# SCH_Espejo_Pcb_tof_2023-06-20.net
KiCad netlist of a schematic drawn in EasyEDA
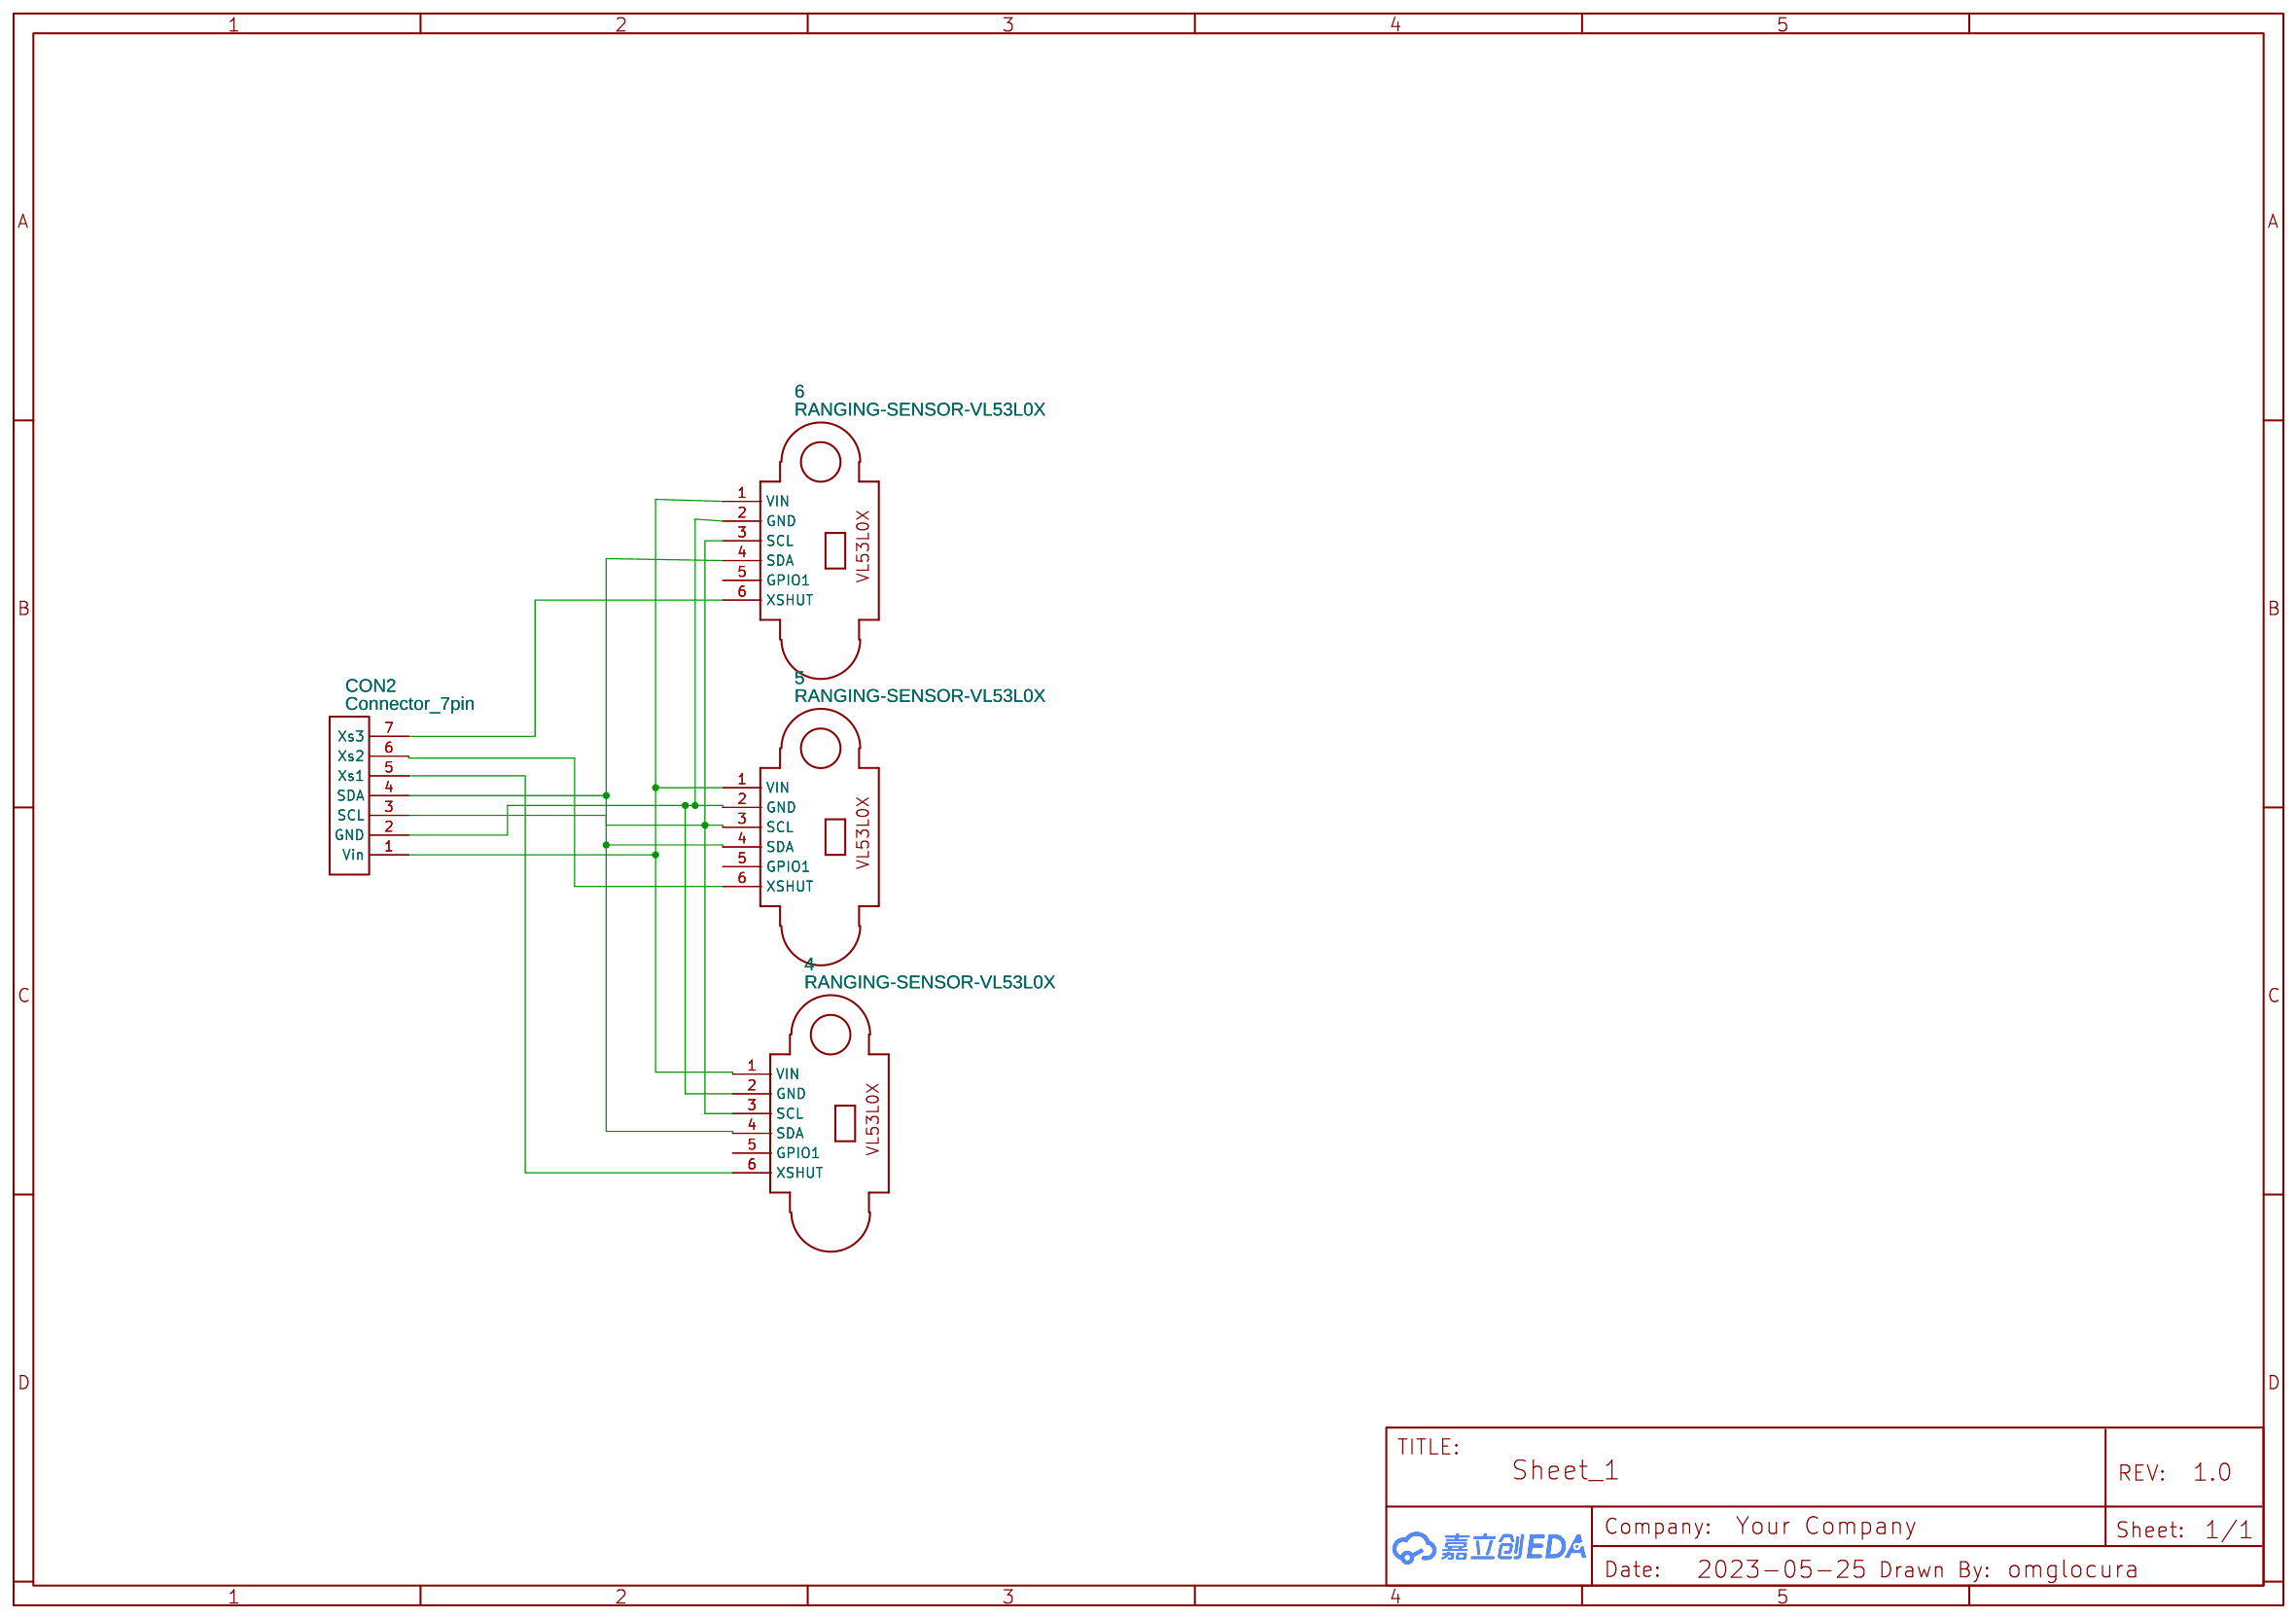
[diagram p0: schematic sheet]

(export (version "E")
  (design (tool "Eeschema 10.0.6"))
  (components
    (comp (ref "4") (value "RANGING-SENSOR-VL53L0X") (libsource (lib "") (part "RANGING-SENSOR-VL53L0X")))
    (comp (ref "5") (value "RANGING-SENSOR-VL53L0X") (libsource (lib "") (part "RANGING-SENSOR-VL53L0X")))
    (comp (ref "6") (value "RANGING-SENSOR-VL53L0X") (libsource (lib "") (part "RANGING-SENSOR-VL53L0X_1")))
    (comp (ref "CON2") (value "Connector_7pin") (libsource (lib "") (part "Connector_7pin")))
  )
  (nets
    (net (code "1") (name "Net-(4-GND)") (class "Default")
      (node (ref "4") (pin "2") (pinfunction "GND_2") (pintype "bidirectional"))
      (node (ref "5") (pin "2") (pinfunction "GND_2") (pintype "bidirectional"))
      (node (ref "6") (pin "2") (pinfunction "GND_2") (pintype "bidirectional"))
      (node (ref "CON2") (pin "2") (pinfunction "GND_2") (pintype "unspecified"))
    )
    (net (code "2") (name "Net-(4-SCL)") (class "Default")
      (node (ref "4") (pin "3") (pinfunction "SCL_3") (pintype "bidirectional"))
      (node (ref "5") (pin "3") (pinfunction "SCL_3") (pintype "bidirectional"))
      (node (ref "6") (pin "3") (pinfunction "SCL_3") (pintype "bidirectional"))
      (node (ref "CON2") (pin "3") (pinfunction "SCL_3") (pintype "unspecified"))
    )
    (net (code "3") (name "Net-(4-SDA)") (class "Default")
      (node (ref "4") (pin "4") (pinfunction "SDA_4") (pintype "bidirectional"))
      (node (ref "5") (pin "4") (pinfunction "SDA_4") (pintype "bidirectional"))
      (node (ref "6") (pin "4") (pinfunction "SDA_4") (pintype "bidirectional"))
      (node (ref "CON2") (pin "4") (pinfunction "SDA_4") (pintype "unspecified"))
    )
    (net (code "4") (name "Net-(4-VIN)") (class "Default")
      (node (ref "4") (pin "1") (pinfunction "VIN_1") (pintype "bidirectional"))
      (node (ref "5") (pin "1") (pinfunction "VIN_1") (pintype "bidirectional"))
      (node (ref "6") (pin "1") (pinfunction "VIN_1") (pintype "bidirectional"))
      (node (ref "CON2") (pin "1") (pinfunction "Vin_1") (pintype "unspecified"))
    )
    (net (code "5") (name "Net-(4-XSHUT)") (class "Default")
      (node (ref "4") (pin "6") (pinfunction "XSHUT_6") (pintype "bidirectional"))
      (node (ref "CON2") (pin "5") (pinfunction "Xs1_5") (pintype "unspecified"))
    )
    (net (code "6") (name "Net-(5-XSHUT)") (class "Default")
      (node (ref "5") (pin "6") (pinfunction "XSHUT_6") (pintype "bidirectional"))
      (node (ref "CON2") (pin "6") (pinfunction "Xs2_6") (pintype "unspecified"))
    )
    (net (code "7") (name "Net-(6-XSHUT)") (class "Default")
      (node (ref "6") (pin "6") (pinfunction "XSHUT_6") (pintype "bidirectional"))
      (node (ref "CON2") (pin "7") (pinfunction "Xs3_7") (pintype "unspecified"))
    )
    (net (code "8") (name "unconnected-(4-GPIO1-Pad5)") (class "Default")
      (node (ref "4") (pin "5") (pinfunction "GPIO1_5") (pintype "bidirectional"))
    )
    (net (code "9") (name "unconnected-(5-GPIO1-Pad5)") (class "Default")
      (node (ref "5") (pin "5") (pinfunction "GPIO1_5") (pintype "bidirectional"))
    )
    (net (code "10") (name "unconnected-(6-GPIO1-Pad5)") (class "Default")
      (node (ref "6") (pin "5") (pinfunction "GPIO1_5") (pintype "bidirectional"))
    )
  )
)
